# minimumSystem_Rizqulloh_faathir_akmal_Y_.net
KiCad netlist of a schematic drawn in EAGLE
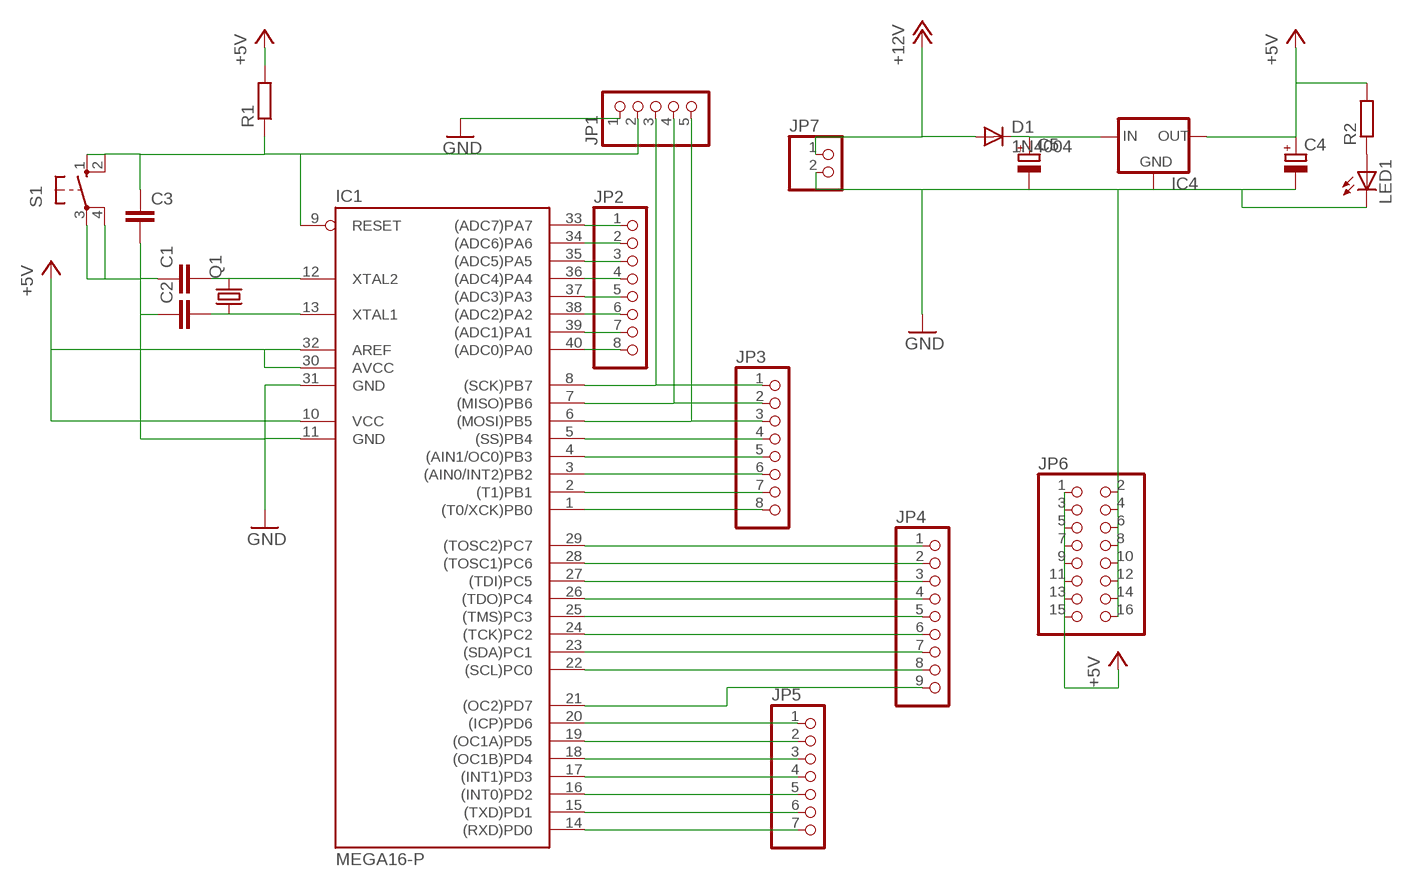
[diagram p0: schematic, sheet 1]

(export (version "E")
  (design (tool "Eeschema 10.0.6"))
  (components
    (comp (ref "C1")
      (value "C-EU025-024X044")
      (footprint "eagle-import:C025-024X044")
      (libsource (lib "eagle-import") (part "C-EU025-024X044"))
    )
    (comp (ref "C2")
      (value "C-EU025-024X044")
      (footprint "eagle-import:C025-024X044")
      (libsource (lib "eagle-import") (part "C-EU025-024X044"))
    )
    (comp (ref "C3")
      (value "C-EU050-025X075")
      (footprint "eagle-import:C050-025X075")
      (libsource (lib "eagle-import") (part "resistor_C-EU050-025X075"))
    )
    (comp (ref "C4")
      (value "CPOL-EUE2.5-5")
      (footprint "eagle-import:E2,5-5")
      (libsource (lib "eagle-import") (part "CPOL-EUE2.5-5"))
    )
    (comp (ref "C5")
      (value "CPOL-EUE2.5-5")
      (footprint "eagle-import:E2,5-5")
      (libsource (lib "eagle-import") (part "CPOL-EUE2.5-5"))
    )
    (comp (ref "D1")
      (value "1N4004")
      (footprint "eagle-import:DO41-10")
      (libsource (lib "eagle-import") (part "1N4004"))
    )
    (comp (ref "IC1")
      (value "MEGA16-P")
      (footprint "eagle-import:DIL40")
      (fields (field (name "MPN") "ATMEGA16-16PU"))
      (libsource (lib "eagle-import") (part "MEGA16-P"))
    )
    (comp (ref "IC4")
      (value "78XXS")
      (footprint "eagle-import:78XXS")
      (libsource (lib "eagle-import") (part "78XXS"))
    )
    (comp (ref "JP1")
      (value "PINHD-1X5")
      (footprint "eagle-import:1X05")
      (libsource (lib "eagle-import") (part "PINHD-1X5"))
    )
    (comp (ref "JP2")
      (value "PINHD-1X8")
      (footprint "eagle-import:1X08")
      (libsource (lib "eagle-import") (part "PINHD-1X8"))
    )
    (comp (ref "JP3")
      (value "PINHD-1X8")
      (footprint "eagle-import:1X08")
      (libsource (lib "eagle-import") (part "PINHD-1X8"))
    )
    (comp (ref "JP4")
      (value "PINHD-1X9")
      (footprint "eagle-import:1X09")
      (libsource (lib "eagle-import") (part "PINHD-1X9"))
    )
    (comp (ref "JP5")
      (value "PINHD-1X7")
      (footprint "eagle-import:1X07")
      (libsource (lib "eagle-import") (part "PINHD-1X7"))
    )
    (comp (ref "JP6")
      (value "PINHD-2X8")
      (footprint "eagle-import:2X08")
      (libsource (lib "eagle-import") (part "PINHD-2X8"))
    )
    (comp (ref "JP7")
      (value "PINHD-1X2")
      (footprint "eagle-import:1X02")
      (libsource (lib "eagle-import") (part "PINHD-1X2"))
    )
    (comp (ref "LED1")
      (value "LED5MM")
      (footprint "eagle-import:LED5MM")
      (libsource (lib "eagle-import") (part "LED5MM"))
    )
    (comp (ref "Q1")
      (value "CRYSTALHC49U-V")
      (footprint "eagle-import:HC49U-V")
      (libsource (lib "eagle-import") (part "CRYSTALHC49U-V"))
    )
    (comp (ref "R1")
      (value "R-EU_0204/7")
      (footprint "eagle-import:0204_7")
      (libsource (lib "eagle-import") (part "R-EU_0204/7"))
    )
    (comp (ref "R2")
      (value "R-EU_0204/7")
      (footprint "eagle-import:0204_7")
      (libsource (lib "eagle-import") (part "R-EU_0204/7"))
    )
    (comp (ref "S1")
      (value "10-XX")
      (footprint "eagle-import:B3F-10XX")
      (fields (field (name "MPN") "B3F-1000"))
      (libsource (lib "eagle-import") (part "10-XX"))
    )
  )
  (nets
    (net (code "1") (name "+5V") (class "Default")
      (node (ref "C4") (pin "+") (pinfunction "+_+") (pintype "passive"))
      (node (ref "IC1") (pin "10") (pinfunction "VCC_10") (pintype "power_in"))
      (node (ref "IC1") (pin "30") (pinfunction "AVCC_30") (pintype "power_in"))
      (node (ref "IC1") (pin "32") (pinfunction "AREF_32") (pintype "passive"))
      (node (ref "IC4") (pin "OUT") (pinfunction "OUT_OUT") (pintype "passive"))
      (node (ref "JP6") (pin "1") (pinfunction "1_1") (pintype "passive"))
      (node (ref "JP6") (pin "11") (pinfunction "11_11") (pintype "passive"))
      (node (ref "JP6") (pin "13") (pinfunction "13_13") (pintype "passive"))
      (node (ref "JP6") (pin "15") (pinfunction "15_15") (pintype "passive"))
      (node (ref "JP6") (pin "3") (pinfunction "3_3") (pintype "passive"))
      (node (ref "JP6") (pin "5") (pinfunction "5_5") (pintype "passive"))
      (node (ref "JP6") (pin "7") (pinfunction "7_7") (pintype "passive"))
      (node (ref "JP6") (pin "9") (pinfunction "9_9") (pintype "passive"))
      (node (ref "R1") (pin "2") (pinfunction "2_2") (pintype "passive"))
      (node (ref "R2") (pin "2") (pinfunction "2_2") (pintype "passive"))
    )
    (net (code "2") (name "+12V") (class "Default")
      (node (ref "D1") (pin "A") (pinfunction "A_A") (pintype "passive"))
      (node (ref "JP7") (pin "1") (pinfunction "1_1") (pintype "passive"))
    )
    (net (code "3") (name "GND") (class "Default")
      (node (ref "C1") (pin "1") (pinfunction "1_1") (pintype "passive"))
      (node (ref "C2") (pin "1") (pinfunction "1_1") (pintype "passive"))
      (node (ref "C3") (pin "2") (pinfunction "2_2") (pintype "passive"))
      (node (ref "C4") (pin "-") (pinfunction "-_-") (pintype "passive"))
      (node (ref "C5") (pin "-") (pinfunction "-_-") (pintype "passive"))
      (node (ref "IC1") (pin "11") (pinfunction "GND_11") (pintype "power_in"))
      (node (ref "IC1") (pin "31") (pinfunction "GND_31") (pintype "power_in"))
      (node (ref "IC4") (pin "GND") (pinfunction "GND_GND") (pintype "input"))
      (node (ref "JP1") (pin "1") (pinfunction "1_1") (pintype "passive"))
      (node (ref "JP6") (pin "10") (pinfunction "10_10") (pintype "passive"))
      (node (ref "JP6") (pin "12") (pinfunction "12_12") (pintype "passive"))
      (node (ref "JP6") (pin "14") (pinfunction "14_14") (pintype "passive"))
      (node (ref "JP6") (pin "16") (pinfunction "16_16") (pintype "passive"))
      (node (ref "JP6") (pin "2") (pinfunction "2_2") (pintype "passive"))
      (node (ref "JP6") (pin "4") (pinfunction "4_4") (pintype "passive"))
      (node (ref "JP6") (pin "6") (pinfunction "6_6") (pintype "passive"))
      (node (ref "JP6") (pin "8") (pinfunction "8_8") (pintype "passive"))
      (node (ref "JP7") (pin "2") (pinfunction "2_2") (pintype "passive"))
      (node (ref "LED1") (pin "K") (pinfunction "C_K") (pintype "passive"))
      (node (ref "S1") (pin "3") (pinfunction "P_3") (pintype "passive"))
      (node (ref "S1") (pin "4") (pinfunction "P1_4") (pintype "passive"))
    )
    (net (code "4") (name "Net-(C5-Pad+)") (class "Default")
      (node (ref "C5") (pin "+") (pinfunction "+_+") (pintype "passive"))
      (node (ref "D1") (pin "C") (pinfunction "C_C") (pintype "passive"))
      (node (ref "IC4") (pin "IN") (pinfunction "IN_IN") (pintype "input"))
    )
    (net (code "5") (name "Net-(IC1-(ADC0)PA0)") (class "Default")
      (node (ref "IC1") (pin "40") (pinfunction "(ADC0)PA0_40") (pintype "bidirectional"))
      (node (ref "JP2") (pin "8") (pinfunction "8_8") (pintype "passive"))
    )
    (net (code "6") (name "Net-(IC1-(ADC1)PA1)") (class "Default")
      (node (ref "IC1") (pin "39") (pinfunction "(ADC1)PA1_39") (pintype "bidirectional"))
      (node (ref "JP2") (pin "7") (pinfunction "7_7") (pintype "passive"))
    )
    (net (code "7") (name "Net-(IC1-(ADC2)PA2)") (class "Default")
      (node (ref "IC1") (pin "38") (pinfunction "(ADC2)PA2_38") (pintype "bidirectional"))
      (node (ref "JP2") (pin "6") (pinfunction "6_6") (pintype "passive"))
    )
    (net (code "8") (name "Net-(IC1-(ADC3)PA3)") (class "Default")
      (node (ref "IC1") (pin "37") (pinfunction "(ADC3)PA3_37") (pintype "bidirectional"))
      (node (ref "JP2") (pin "5") (pinfunction "5_5") (pintype "passive"))
    )
    (net (code "9") (name "Net-(IC1-(ADC4)PA4)") (class "Default")
      (node (ref "IC1") (pin "36") (pinfunction "(ADC4)PA4_36") (pintype "bidirectional"))
      (node (ref "JP2") (pin "4") (pinfunction "4_4") (pintype "passive"))
    )
    (net (code "10") (name "Net-(IC1-(ADC5)PA5)") (class "Default")
      (node (ref "IC1") (pin "35") (pinfunction "(ADC5)PA5_35") (pintype "bidirectional"))
      (node (ref "JP2") (pin "3") (pinfunction "3_3") (pintype "passive"))
    )
    (net (code "11") (name "Net-(IC1-(ADC6)PA6)") (class "Default")
      (node (ref "IC1") (pin "34") (pinfunction "(ADC6)PA6_34") (pintype "bidirectional"))
      (node (ref "JP2") (pin "2") (pinfunction "2_2") (pintype "passive"))
    )
    (net (code "12") (name "Net-(IC1-(ADC7)PA7)") (class "Default")
      (node (ref "IC1") (pin "33") (pinfunction "(ADC7)PA7_33") (pintype "bidirectional"))
      (node (ref "JP2") (pin "1") (pinfunction "1_1") (pintype "passive"))
    )
    (net (code "13") (name "Net-(IC1-(AIN0{slash}INT2)PB2)") (class "Default")
      (node (ref "IC1") (pin "3") (pinfunction "(AIN0/INT2)PB2_3") (pintype "bidirectional"))
      (node (ref "JP3") (pin "6") (pinfunction "6_6") (pintype "passive"))
    )
    (net (code "14") (name "Net-(IC1-(AIN1{slash}OC0)PB3)") (class "Default")
      (node (ref "IC1") (pin "4") (pinfunction "(AIN1/OC0)PB3_4") (pintype "bidirectional"))
      (node (ref "JP3") (pin "5") (pinfunction "5_5") (pintype "passive"))
    )
    (net (code "15") (name "Net-(IC1-(ICP)PD6)") (class "Default")
      (node (ref "IC1") (pin "20") (pinfunction "(ICP)PD6_20") (pintype "bidirectional"))
      (node (ref "JP5") (pin "1") (pinfunction "1_1") (pintype "passive"))
    )
    (net (code "16") (name "Net-(IC1-(INT0)PD2)") (class "Default")
      (node (ref "IC1") (pin "16") (pinfunction "(INT0)PD2_16") (pintype "bidirectional"))
      (node (ref "JP5") (pin "5") (pinfunction "5_5") (pintype "passive"))
    )
    (net (code "17") (name "Net-(IC1-(INT1)PD3)") (class "Default")
      (node (ref "IC1") (pin "17") (pinfunction "(INT1)PD3_17") (pintype "bidirectional"))
      (node (ref "JP5") (pin "4") (pinfunction "4_4") (pintype "passive"))
    )
    (net (code "18") (name "Net-(IC1-(MISO)PB6)") (class "Default")
      (node (ref "IC1") (pin "7") (pinfunction "(MISO)PB6_7") (pintype "bidirectional"))
      (node (ref "JP1") (pin "4") (pinfunction "4_4") (pintype "passive"))
      (node (ref "JP3") (pin "2") (pinfunction "2_2") (pintype "passive"))
    )
    (net (code "19") (name "Net-(IC1-(MOSI)PB5)") (class "Default")
      (node (ref "IC1") (pin "6") (pinfunction "(MOSI)PB5_6") (pintype "bidirectional"))
      (node (ref "JP1") (pin "5") (pinfunction "5_5") (pintype "passive"))
      (node (ref "JP3") (pin "3") (pinfunction "3_3") (pintype "passive"))
    )
    (net (code "20") (name "Net-(IC1-(OC1A)PD5)") (class "Default")
      (node (ref "IC1") (pin "19") (pinfunction "(OC1A)PD5_19") (pintype "bidirectional"))
      (node (ref "JP5") (pin "2") (pinfunction "2_2") (pintype "passive"))
    )
    (net (code "21") (name "Net-(IC1-(OC1B)PD4)") (class "Default")
      (node (ref "IC1") (pin "18") (pinfunction "(OC1B)PD4_18") (pintype "bidirectional"))
      (node (ref "JP5") (pin "3") (pinfunction "3_3") (pintype "passive"))
    )
    (net (code "22") (name "Net-(IC1-(OC2)PD7)") (class "Default")
      (node (ref "IC1") (pin "21") (pinfunction "(OC2)PD7_21") (pintype "bidirectional"))
      (node (ref "JP4") (pin "9") (pinfunction "9_9") (pintype "passive"))
    )
    (net (code "23") (name "Net-(IC1-(RXD)PD0)") (class "Default")
      (node (ref "IC1") (pin "14") (pinfunction "(RXD)PD0_14") (pintype "bidirectional"))
      (node (ref "JP5") (pin "7") (pinfunction "7_7") (pintype "passive"))
    )
    (net (code "24") (name "Net-(IC1-(SCK)PB7)") (class "Default")
      (node (ref "IC1") (pin "8") (pinfunction "(SCK)PB7_8") (pintype "bidirectional"))
      (node (ref "JP1") (pin "3") (pinfunction "3_3") (pintype "passive"))
      (node (ref "JP3") (pin "1") (pinfunction "1_1") (pintype "passive"))
    )
    (net (code "25") (name "Net-(IC1-(SCL)PC0)") (class "Default")
      (node (ref "IC1") (pin "22") (pinfunction "(SCL)PC0_22") (pintype "bidirectional"))
      (node (ref "JP4") (pin "8") (pinfunction "8_8") (pintype "passive"))
    )
    (net (code "26") (name "Net-(IC1-(SDA)PC1)") (class "Default")
      (node (ref "IC1") (pin "23") (pinfunction "(SDA)PC1_23") (pintype "bidirectional"))
      (node (ref "JP4") (pin "7") (pinfunction "7_7") (pintype "passive"))
    )
    (net (code "27") (name "Net-(IC1-(SS)PB4)") (class "Default")
      (node (ref "IC1") (pin "5") (pinfunction "(SS)PB4_5") (pintype "bidirectional"))
      (node (ref "JP3") (pin "4") (pinfunction "4_4") (pintype "passive"))
    )
    (net (code "28") (name "Net-(IC1-(T0{slash}XCK)PB0)") (class "Default")
      (node (ref "IC1") (pin "1") (pinfunction "(T0/XCK)PB0_1") (pintype "bidirectional"))
      (node (ref "JP3") (pin "8") (pinfunction "8_8") (pintype "passive"))
    )
    (net (code "29") (name "Net-(IC1-(T1)PB1)") (class "Default")
      (node (ref "IC1") (pin "2") (pinfunction "(T1)PB1_2") (pintype "bidirectional"))
      (node (ref "JP3") (pin "7") (pinfunction "7_7") (pintype "passive"))
    )
    (net (code "30") (name "Net-(IC1-(TCK)PC2)") (class "Default")
      (node (ref "IC1") (pin "24") (pinfunction "(TCK)PC2_24") (pintype "bidirectional"))
      (node (ref "JP4") (pin "6") (pinfunction "6_6") (pintype "passive"))
    )
    (net (code "31") (name "Net-(IC1-(TDI)PC5)") (class "Default")
      (node (ref "IC1") (pin "27") (pinfunction "(TDI)PC5_27") (pintype "bidirectional"))
      (node (ref "JP4") (pin "3") (pinfunction "3_3") (pintype "passive"))
    )
    (net (code "32") (name "Net-(IC1-(TDO)PC4)") (class "Default")
      (node (ref "IC1") (pin "26") (pinfunction "(TDO)PC4_26") (pintype "bidirectional"))
      (node (ref "JP4") (pin "4") (pinfunction "4_4") (pintype "passive"))
    )
    (net (code "33") (name "Net-(IC1-(TMS)PC3)") (class "Default")
      (node (ref "IC1") (pin "25") (pinfunction "(TMS)PC3_25") (pintype "bidirectional"))
      (node (ref "JP4") (pin "5") (pinfunction "5_5") (pintype "passive"))
    )
    (net (code "34") (name "Net-(IC1-(TOSC1)PC6)") (class "Default")
      (node (ref "IC1") (pin "28") (pinfunction "(TOSC1)PC6_28") (pintype "bidirectional"))
      (node (ref "JP4") (pin "2") (pinfunction "2_2") (pintype "passive"))
    )
    (net (code "35") (name "Net-(IC1-(TOSC2)PC7)") (class "Default")
      (node (ref "IC1") (pin "29") (pinfunction "(TOSC2)PC7_29") (pintype "bidirectional"))
      (node (ref "JP4") (pin "1") (pinfunction "1_1") (pintype "passive"))
    )
    (net (code "36") (name "Net-(IC1-(TXD)PD1)") (class "Default")
      (node (ref "IC1") (pin "15") (pinfunction "(TXD)PD1_15") (pintype "bidirectional"))
      (node (ref "JP5") (pin "6") (pinfunction "6_6") (pintype "passive"))
    )
    (net (code "37") (name "Net-(IC1-RESET)") (class "Default")
      (node (ref "C3") (pin "1") (pinfunction "1_1") (pintype "passive"))
      (node (ref "IC1") (pin "9") (pinfunction "RESET_9") (pintype "input"))
      (node (ref "JP1") (pin "2") (pinfunction "2_2") (pintype "passive"))
      (node (ref "R1") (pin "1") (pinfunction "1_1") (pintype "passive"))
      (node (ref "S1") (pin "1") (pinfunction "S_1") (pintype "passive"))
      (node (ref "S1") (pin "2") (pinfunction "S1_2") (pintype "passive"))
    )
    (net (code "38") (name "Net-(IC1-XTAL1)") (class "Default")
      (node (ref "C2") (pin "2") (pinfunction "2_2") (pintype "passive"))
      (node (ref "IC1") (pin "13") (pinfunction "XTAL1_13") (pintype "bidirectional"))
      (node (ref "Q1") (pin "1") (pinfunction "1_1") (pintype "passive"))
    )
    (net (code "39") (name "Net-(IC1-XTAL2)") (class "Default")
      (node (ref "C1") (pin "2") (pinfunction "2_2") (pintype "passive"))
      (node (ref "IC1") (pin "12") (pinfunction "XTAL2_12") (pintype "bidirectional"))
      (node (ref "Q1") (pin "2") (pinfunction "2_2") (pintype "passive"))
    )
    (net (code "40") (name "Net-(LED1-PadA)") (class "Default")
      (node (ref "LED1") (pin "A") (pinfunction "A_A") (pintype "passive"))
      (node (ref "R2") (pin "1") (pinfunction "1_1") (pintype "passive"))
    )
  )
)
